# LaserDiode_Analog.net
KiCad netlist of a schematic drawn in Altium Designer
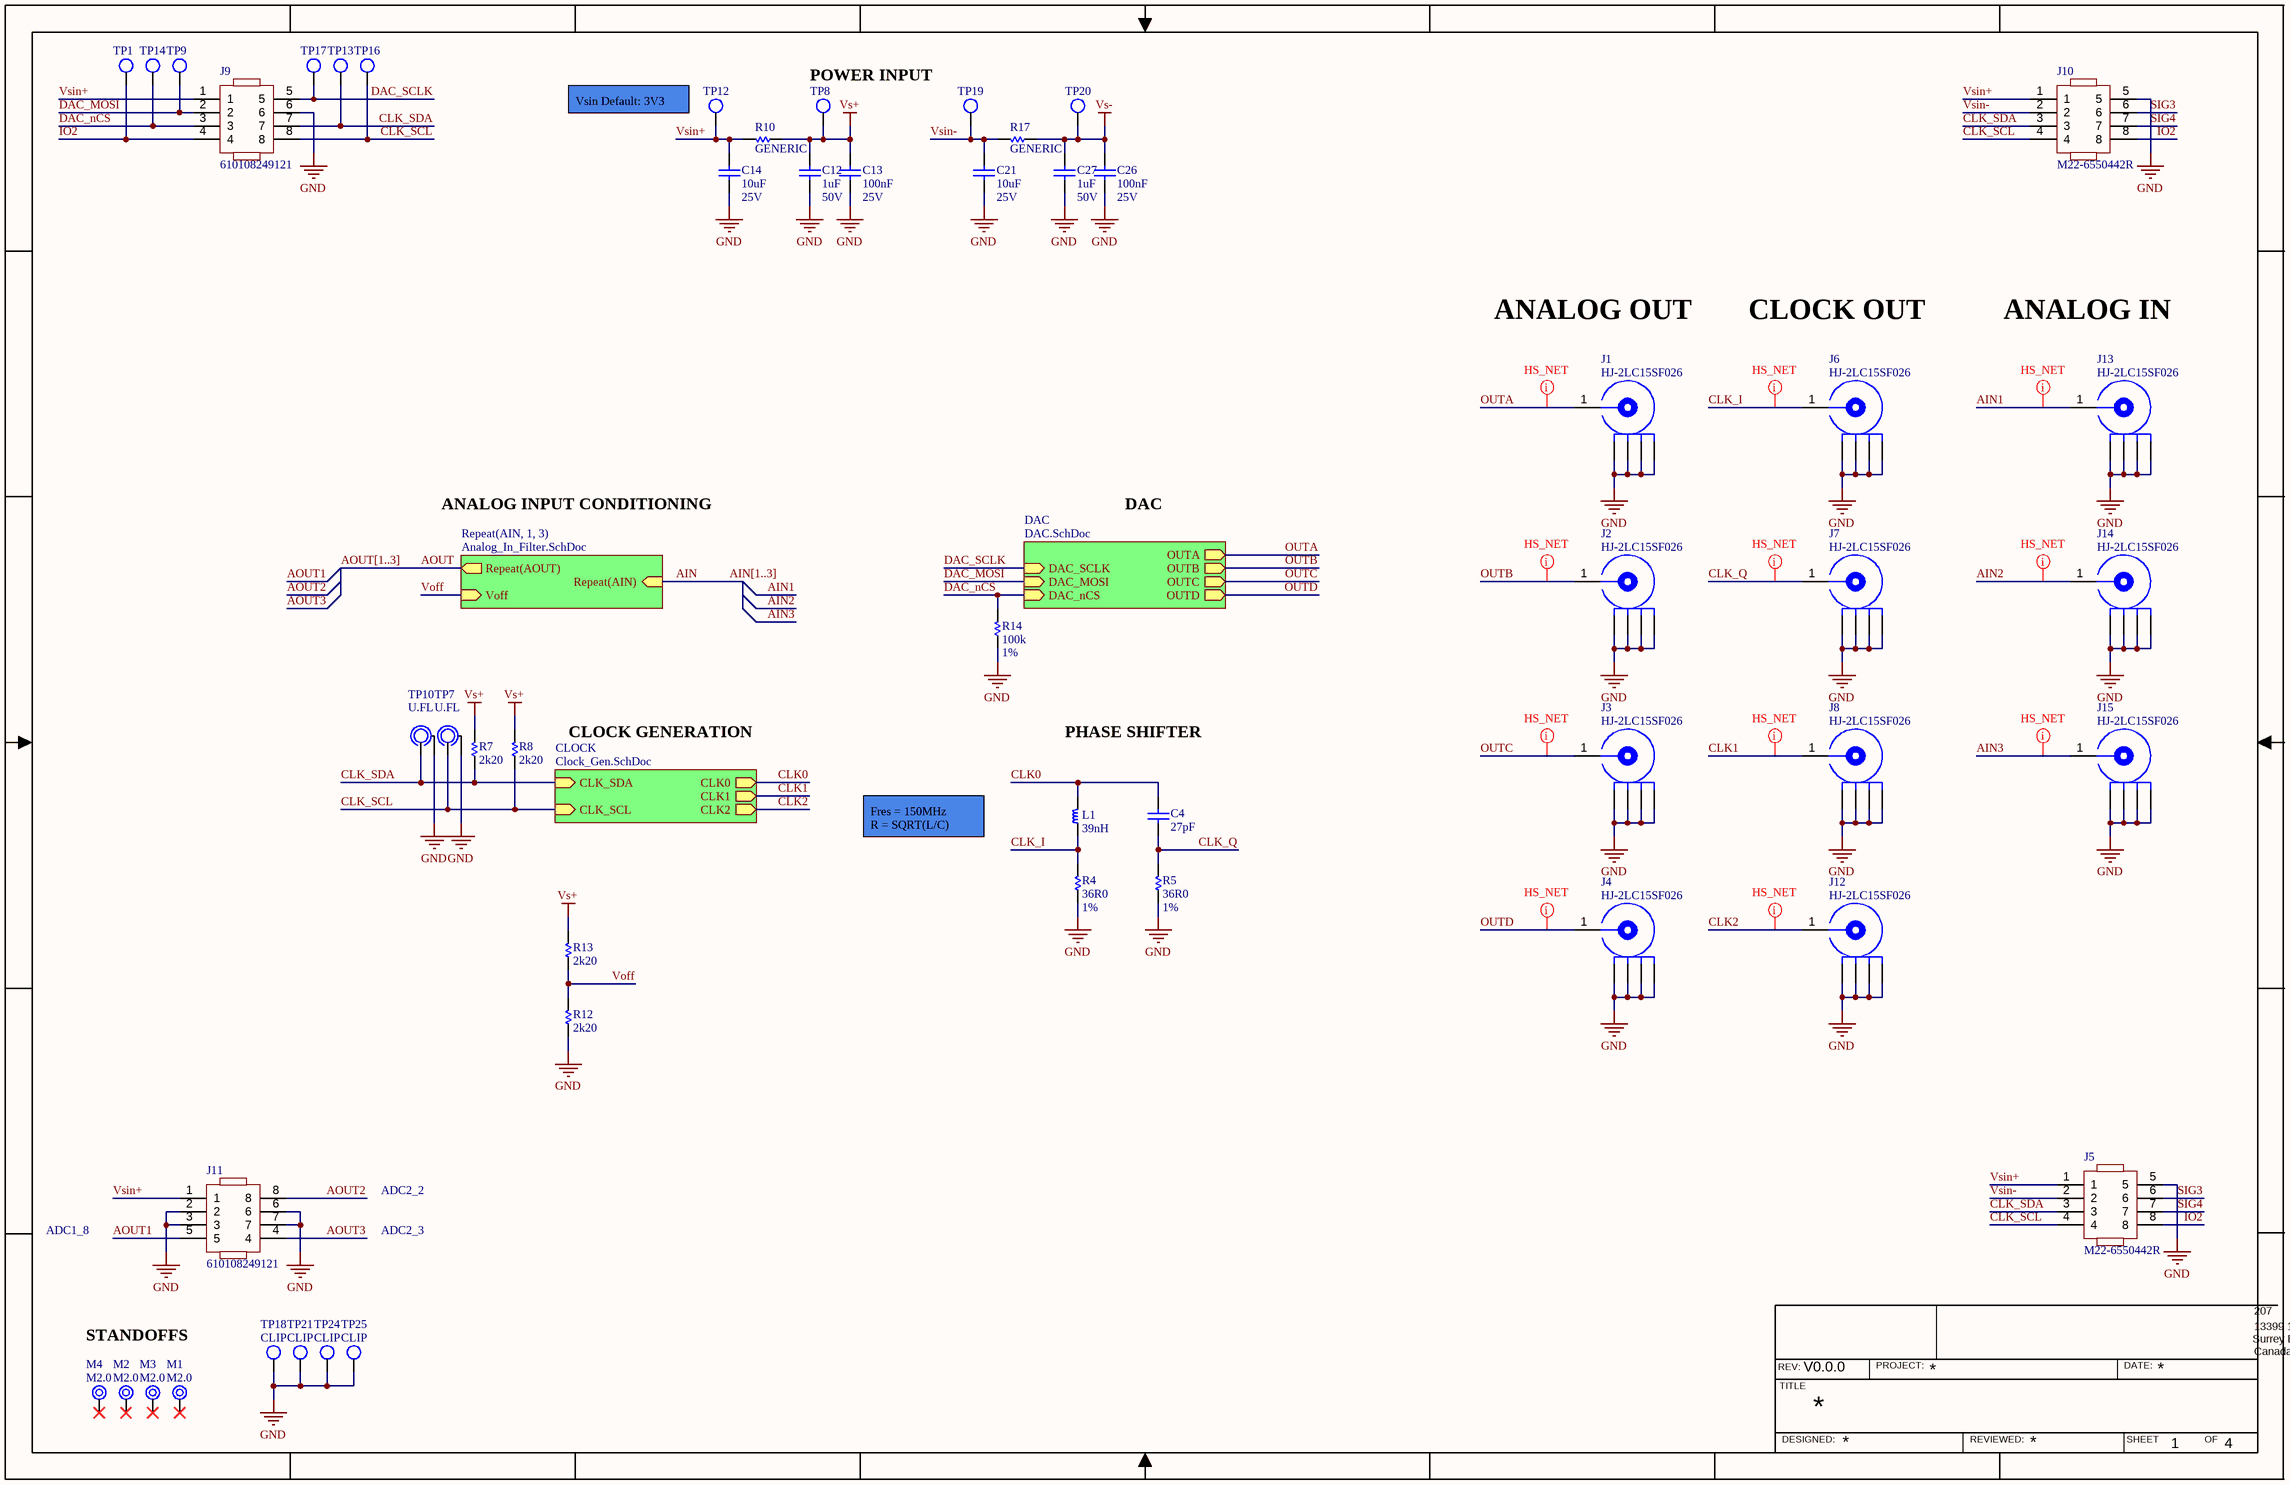
[diagram p0: LaserDiode_Analog.SchDoc]

(export (version "E")
  (design (tool "Eeschema 10.0.6"))
  (components
    (comp (ref "C4")
      (value "27pF")
      (footprint "C0402")
      (description "贴片陶瓷电容  27pF ±5% 50V C0G(NP0) 0402")
      (fields
        (field (name "MANUFACTURER") "Samsung")
        (field (name "MANUFACTURER PART NUMBER") "CL05C270JB5NNNC")
      )
      (libsource (lib "LaserDiode_Analog") (part "CAP CER 27pF 50V C0G 0402"))
    )
    (comp (ref "C12")
      (value "1uF")
      (footprint "c0603")
      (description "Multilayer Ceramic Capacitors (High dielectric type), 50V, 1 uF, ± 10 %, 0603, X5R, RoHS")
      (fields
        (field (name "MANUFACTURER") "Taiyo Yuden")
        (field (name "MANUFACTURER PART NUMBER") "UMK107BJ105KA-T")
        (field (name "VOLTAGE RATING") "50V")
      )
      (libsource (lib "OPAMP_DEV_SOT5_6-23") (part "CAP CER 1uF 50V X5R 0603"))
    )
    (comp (ref "C13")
      (value "100nF")
      (footprint "C0402")
      (description "Cap Ceramic 0.1uF 25V X5R 10% Pad SMD 0402 85°C T/R / Multi Layer Ceramic Capacitor (MLCC)")
      (fields
        (field (name "MANUFACTURER") "Samsung")
        (field (name "MANUFACTURER PART NUMBER") "CL05A104KA5NNNC")
        (field (name "VOLTAGE RATING") "25V")
      )
      (libsource (lib "OPAMP_DEV_SOT5_6-23") (part "CAP CER 100nF 25V X5R 0402"))
    )
    (comp (ref "C14")
      (value "10uF")
      (footprint "c0805")
      (description "Cap Ceramic 10uF 25V X5R 10% SMD 0805 85°C Embossed T/R")
      (fields
        (field (name "MANUFACTURER") "Samsung")
        (field (name "MANUFACTURER PART NUMBER") "CL21A106KAYNNNE")
        (field (name "VOLTAGE RATING") "25V")
      )
      (libsource (lib "OPAMP_DEV_SOT5_6-23") (part "CAP CER 10uF 25V X5R 0805"))
    )
    (comp (ref "C21")
      (value "10uF")
      (footprint "c0805")
      (description "Cap Ceramic 10uF 25V X5R 10% SMD 0805 85°C Embossed T/R")
      (fields
        (field (name "MANUFACTURER") "Samsung")
        (field (name "MANUFACTURER PART NUMBER") "CL21A106KAYNNNE")
        (field (name "VOLTAGE RATING") "25V")
      )
      (libsource (lib "OPAMP_DEV_SOT5_6-23") (part "CAP CER 10uF 25V X5R 0805"))
    )
    (comp (ref "C26")
      (value "100nF")
      (footprint "C0402")
      (description "Cap Ceramic 0.1uF 25V X5R 10% Pad SMD 0402 85°C T/R / Multi Layer Ceramic Capacitor (MLCC)")
      (fields
        (field (name "MANUFACTURER") "Samsung")
        (field (name "MANUFACTURER PART NUMBER") "CL05A104KA5NNNC")
        (field (name "VOLTAGE RATING") "25V")
      )
      (libsource (lib "OPAMP_DEV_SOT5_6-23") (part "CAP CER 100nF 25V X5R 0402"))
    )
    (comp (ref "C27")
      (value "1uF")
      (footprint "c0603")
      (description "Multilayer Ceramic Capacitors (High dielectric type), 50V, 1 uF, ± 10 %, 0603, X5R, RoHS")
      (fields
        (field (name "MANUFACTURER") "Taiyo Yuden")
        (field (name "MANUFACTURER PART NUMBER") "UMK107BJ105KA-T")
        (field (name "VOLTAGE RATING") "50V")
      )
      (libsource (lib "OPAMP_DEV_SOT5_6-23") (part "CAP CER 1uF 50V X5R 0603"))
    )
    (comp (ref "J1")
      (value "HJ-2LC15SF026")
      (footprint "SMA TH RA BORE")
      (libsource (lib "LaserDiode_Analog") (part "CON SMA BORE SMD RA HJ-2LC15SF026"))
    )
    (comp (ref "J2")
      (value "HJ-2LC15SF026")
      (footprint "SMA TH RA BORE")
      (libsource (lib "LaserDiode_Analog") (part "CON SMA BORE SMD RA HJ-2LC15SF026"))
    )
    (comp (ref "J3")
      (value "HJ-2LC15SF026")
      (footprint "SMA TH RA BORE")
      (libsource (lib "LaserDiode_Analog") (part "CON SMA BORE SMD RA HJ-2LC15SF026"))
    )
    (comp (ref "J4")
      (value "HJ-2LC15SF026")
      (footprint "SMA TH RA BORE")
      (libsource (lib "LaserDiode_Analog") (part "CON SMA BORE SMD RA HJ-2LC15SF026"))
    )
    (comp (ref "J5")
      (value "M22-6550442R")
      (footprint "CONN HDR 08 FEMALE RA 2ROW")
      (description "Conn Socket Strip RCP 8 POS 2mm Solder RA SMD T/R")
      (fields (field (name "MANUFACTURER") "Harwin"))
      (libsource (lib "OPAMP_DEV_SOT5_6-23") (part "CONN HDR 08 FEMALE RA 2 ROW"))
    )
    (comp (ref "J6")
      (value "HJ-2LC15SF026")
      (footprint "SMA TH RA BORE")
      (libsource (lib "LaserDiode_Analog") (part "CON SMA BORE SMD RA HJ-2LC15SF026"))
    )
    (comp (ref "J7")
      (value "HJ-2LC15SF026")
      (footprint "SMA TH RA BORE")
      (libsource (lib "LaserDiode_Analog") (part "CON SMA BORE SMD RA HJ-2LC15SF026"))
    )
    (comp (ref "J8")
      (value "HJ-2LC15SF026")
      (footprint "SMA TH RA BORE")
      (libsource (lib "LaserDiode_Analog") (part "CON SMA BORE SMD RA HJ-2LC15SF026"))
    )
    (comp (ref "J9")
      (value "610108249121")
      (footprint "CONN HDR 08 MALE RA 2ROW - duplicate")
      (description "SMT Angled Pin Header WR-PHD, Pitch 2.54 mm, Dual Row, 8 pins")
      (fields (field (name "MANUFACTURER") "Wurth Electronics"))
      (libsource (lib "") (part "CONN HDR 08 MALE RA 2 ROW_1"))
    )
    (comp (ref "J10")
      (value "M22-6550442R")
      (footprint "CONN HDR 08 FEMALE RA 2ROW")
      (description "Conn Socket Strip RCP 8 POS 2mm Solder RA SMD T/R")
      (fields (field (name "MANUFACTURER") "Harwin"))
      (libsource (lib "OPAMP_DEV_SOT5_6-23") (part "CONN HDR 08 FEMALE RA 2 ROW"))
    )
    (comp (ref "J11")
      (value "610108249121")
      (footprint "CONN HDR 08 MALE RA 2ROW - duplicate")
      (description "SMT Angled Pin Header WR-PHD, Pitch 2.54 mm, Dual Row, 8 pins")
      (fields (field (name "MANUFACTURER") "Wurth Electronics"))
      (libsource (lib "OPAMP_DEV_SOT5_6-23") (part "CONN HDR 08 MALE RA 2 ROW"))
    )
    (comp (ref "J12")
      (value "HJ-2LC15SF026")
      (footprint "SMA TH RA BORE")
      (libsource (lib "LaserDiode_Analog") (part "CON SMA BORE SMD RA HJ-2LC15SF026"))
    )
    (comp (ref "J13")
      (value "HJ-2LC15SF026")
      (footprint "SMA TH RA BORE")
      (libsource (lib "LaserDiode_Analog") (part "CON SMA BORE SMD RA HJ-2LC15SF026"))
    )
    (comp (ref "J14")
      (value "HJ-2LC15SF026")
      (footprint "SMA TH RA BORE")
      (libsource (lib "LaserDiode_Analog") (part "CON SMA BORE SMD RA HJ-2LC15SF026"))
    )
    (comp (ref "J15")
      (value "HJ-2LC15SF026")
      (footprint "SMA TH RA BORE")
      (libsource (lib "LaserDiode_Analog") (part "CON SMA BORE SMD RA HJ-2LC15SF026"))
    )
    (comp (ref "L1")
      (value "39nH")
      (footprint "L0402")
      (description "Inductor RF Chip Multi-Layer 0.039uH 5% 100MHz 8Q-Factor Ceramic 0.15A 1.2Ohm DCR 0402 T/R")
      (fields (field (name "TOLERANCE") "5%"))
      (libsource (lib "LaserDiode_Analog") (part "IND HF 39nH 5% 150mA 1R2 0402"))
    )
    (comp (ref "M1")
      (value "M2.0")
      (footprint "MECH M2.0 UNPLATED")
      (libsource (lib "OPAMP_DEV_SOT5_6-23") (part "MECH M2.0 UNPLATED"))
    )
    (comp (ref "M2")
      (value "M2.0")
      (footprint "MECH M2.0 UNPLATED")
      (libsource (lib "OPAMP_DEV_SOT5_6-23") (part "MECH M2.0 UNPLATED"))
    )
    (comp (ref "M3")
      (value "M2.0")
      (footprint "MECH M2.0 UNPLATED")
      (libsource (lib "OPAMP_DEV_SOT5_6-23") (part "MECH M2.0 UNPLATED"))
    )
    (comp (ref "M4")
      (value "M2.0")
      (footprint "MECH M2.0 UNPLATED")
      (libsource (lib "OPAMP_DEV_SOT5_6-23") (part "MECH M2.0 UNPLATED"))
    )
    (comp (ref "R4")
      (value "36R0")
      (footprint "R0402")
      (description "Res Thick Film 0402 36 Ohm 1% 0.063W(1/16W) ±100ppm/°C Pad SMD T/R")
      (fields (field (name "TOLERANCE") "1%"))
      (libsource (lib "LaserDiode_Analog") (part "RES 36R0 1% 63mW 0402"))
    )
    (comp (ref "R5")
      (value "36R0")
      (footprint "R0402")
      (description "Res Thick Film 0402 36 Ohm 1% 0.063W(1/16W) ±100ppm/°C Pad SMD T/R")
      (fields (field (name "TOLERANCE") "1%"))
      (libsource (lib "LaserDiode_Analog") (part "RES 36R0 1% 63mW 0402"))
    )
    (comp (ref "R7")
      (value "2k20")
      (footprint "R0402")
      (description "贴片电阻 2200Ω ± 1.00% 0.0625W ± 100ppm/℃ 0402")
      (fields
        (field (name "MANUFACTURER") "Yageo")
        (field (name "MANUFACTURER PART NUMBER") "RC0402FR-072K2L")
      )
      (libsource (lib "LaserDiode_Analog") (part "RES 2k20 1% 63mW 0402"))
    )
    (comp (ref "R8")
      (value "2k20")
      (footprint "R0402")
      (description "贴片电阻 2200Ω ± 1.00% 0.0625W ± 100ppm/℃ 0402")
      (fields
        (field (name "MANUFACTURER") "Yageo")
        (field (name "MANUFACTURER PART NUMBER") "RC0402FR-072K2L")
      )
      (libsource (lib "LaserDiode_Analog") (part "RES 2k20 1% 63mW 0402"))
    )
    (comp (ref "R10")
      (value "GENERIC")
      (footprint "R0603")
      (libsource (lib "OPAMP_DEV_SOT5_6-23") (part "RES GENERIC 0603"))
    )
    (comp (ref "R12")
      (value "2k20")
      (footprint "R0402")
      (description "贴片电阻 2200Ω ± 1.00% 0.0625W ± 100ppm/℃ 0402")
      (fields
        (field (name "MANUFACTURER") "Yageo")
        (field (name "MANUFACTURER PART NUMBER") "RC0402FR-072K2L")
      )
      (libsource (lib "LaserDiode_Analog") (part "RES 2k20 1% 63mW 0402"))
    )
    (comp (ref "R13")
      (value "2k20")
      (footprint "R0402")
      (description "贴片电阻 2200Ω ± 1.00% 0.0625W ± 100ppm/℃ 0402")
      (fields
        (field (name "MANUFACTURER") "Yageo")
        (field (name "MANUFACTURER PART NUMBER") "RC0402FR-072K2L")
      )
      (libsource (lib "LaserDiode_Analog") (part "RES 2k20 1% 63mW 0402"))
    )
    (comp (ref "R14")
      (value "100k")
      (footprint "r0402")
      (description "Res Thick Film 0402 100K Ohm 1% 0.063W ±100ppm/°C Molded SMD Paper T/R")
      (fields
        (field (name "MANUFACTURER") "Stackpole Electronics")
        (field (name "MANUFACTURER PART NUMBER") "RMCF0402FT100K")
        (field (name "TOLERANCE") "1%")
      )
      (libsource (lib "LaserDiode_Analog") (part "RES 100k 1% 63mW 0402"))
    )
    (comp (ref "R17")
      (value "GENERIC")
      (footprint "R0603")
      (libsource (lib "OPAMP_DEV_SOT5_6-23") (part "RES GENERIC 0603"))
    )
    (comp (ref "TP1")
      (value "1mm")
      (footprint "TESTPOINT_SMT")
      (description "SMT testpoint")
      (libsource (lib "OPAMP_DEV_SOT5_6-23") (part "TP 1mm"))
    )
    (comp (ref "TP7")
      (value "U.FL")
      (footprint "U.FL")
      (description "CONN U.FL RCPT STR 50 OHM SMD")
      (fields
        (field (name "MANUFACTURER") "Hirose")
        (field (name "MANUFACTURER PART NUMBER") "U.FL-R-SMT-1(80)")
      )
      (libsource (lib "OPAMP_DEV_SOT5_6-23") (part "TP U.FL"))
    )
    (comp (ref "TP8")
      (value "1mm")
      (footprint "TESTPOINT_SMT")
      (description "SMT testpoint")
      (libsource (lib "OPAMP_DEV_SOT5_6-23") (part "TP 1mm"))
    )
    (comp (ref "TP9")
      (value "1mm")
      (footprint "TESTPOINT_SMT")
      (description "SMT testpoint")
      (libsource (lib "OPAMP_DEV_SOT5_6-23") (part "TP 1mm"))
    )
    (comp (ref "TP10")
      (value "U.FL")
      (footprint "U.FL")
      (description "CONN U.FL RCPT STR 50 OHM SMD")
      (fields
        (field (name "MANUFACTURER") "Hirose")
        (field (name "MANUFACTURER PART NUMBER") "U.FL-R-SMT-1(80)")
      )
      (libsource (lib "OPAMP_DEV_SOT5_6-23") (part "TP U.FL"))
    )
    (comp (ref "TP12")
      (value "1mm")
      (footprint "TESTPOINT_SMT")
      (description "SMT testpoint")
      (libsource (lib "OPAMP_DEV_SOT5_6-23") (part "TP 1mm"))
    )
    (comp (ref "TP13")
      (value "1mm")
      (footprint "TESTPOINT_SMT")
      (description "SMT testpoint")
      (libsource (lib "OPAMP_DEV_SOT5_6-23") (part "TP 1mm"))
    )
    (comp (ref "TP14")
      (value "1mm")
      (footprint "TESTPOINT_SMT")
      (description "SMT testpoint")
      (libsource (lib "OPAMP_DEV_SOT5_6-23") (part "TP 1mm"))
    )
    (comp (ref "TP16")
      (value "1mm")
      (footprint "TESTPOINT_SMT")
      (description "SMT testpoint")
      (libsource (lib "OPAMP_DEV_SOT5_6-23") (part "TP 1mm"))
    )
    (comp (ref "TP17")
      (value "1mm")
      (footprint "TESTPOINT_SMT")
      (description "SMT testpoint")
      (libsource (lib "OPAMP_DEV_SOT5_6-23") (part "TP 1mm"))
    )
    (comp (ref "TP18")
      (value "CLIP")
      (footprint "TESTPOINT_CLIP_1206")
      (description "Current Sense Resistors - SMD CHIP CHECKER HT=2.0 1206")
      (fields (field (name "MANUFACTURER") "KOA Speer") (field (name "MANUFACTURER PART NUMBER") "RCWCTE"))
      (libsource (lib "LaserDiode_Analog") (part "TP CLIP 1206 RCWCTE"))
    )
    (comp (ref "TP19")
      (value "1mm")
      (footprint "TESTPOINT_SMT")
      (description "SMT testpoint")
      (libsource (lib "OPAMP_DEV_SOT5_6-23") (part "TP 1mm"))
    )
    (comp (ref "TP20")
      (value "1mm")
      (footprint "TESTPOINT_SMT")
      (description "SMT testpoint")
      (libsource (lib "OPAMP_DEV_SOT5_6-23") (part "TP 1mm"))
    )
    (comp (ref "TP21")
      (value "CLIP")
      (footprint "TESTPOINT_CLIP_1206")
      (description "Current Sense Resistors - SMD CHIP CHECKER HT=2.0 1206")
      (fields (field (name "MANUFACTURER") "KOA Speer") (field (name "MANUFACTURER PART NUMBER") "RCWCTE"))
      (libsource (lib "LaserDiode_Analog") (part "TP CLIP 1206 RCWCTE"))
    )
    (comp (ref "TP24")
      (value "CLIP")
      (footprint "TESTPOINT_CLIP_1206")
      (description "Current Sense Resistors - SMD CHIP CHECKER HT=2.0 1206")
      (fields (field (name "MANUFACTURER") "KOA Speer") (field (name "MANUFACTURER PART NUMBER") "RCWCTE"))
      (libsource (lib "LaserDiode_Analog") (part "TP CLIP 1206 RCWCTE"))
    )
    (comp (ref "TP25")
      (value "CLIP")
      (footprint "TESTPOINT_CLIP_1206")
      (description "Current Sense Resistors - SMD CHIP CHECKER HT=2.0 1206")
      (fields (field (name "MANUFACTURER") "KOA Speer") (field (name "MANUFACTURER PART NUMBER") "RCWCTE"))
      (libsource (lib "LaserDiode_Analog") (part "TP CLIP 1206 RCWCTE"))
    )
  )
  (nets
    (net (code "2") (name "/AIN1") (class "Default")
      (node (ref "J13") (pin "1") (pinfunction "1_1") (pintype "passive"))
    )
    (net (code "3") (name "/AIN2") (class "Default")
      (node (ref "J14") (pin "1") (pinfunction "1_1") (pintype "passive"))
    )
    (net (code "4") (name "/AIN3") (class "Default")
      (node (ref "J15") (pin "1") (pinfunction "1_1") (pintype "passive"))
    )
    (net (code "7") (name "/AOUT1") (class "Default")
      (node (ref "J11") (pin "5") (pinfunction "5_5") (pintype "passive"))
    )
    (net (code "8") (name "/AOUT2") (class "Default")
      (node (ref "J11") (pin "8") (pinfunction "8_8") (pintype "passive"))
    )
    (net (code "9") (name "/AOUT3") (class "Default")
      (node (ref "J11") (pin "4") (pinfunction "4_4") (pintype "passive"))
    )
    (net (code "11") (name "/CLK0") (class "Default")
      (node (ref "C4") (pin "2") (pinfunction "2_2") (pintype "passive"))
      (node (ref "L1") (pin "1") (pinfunction "1_1") (pintype "passive"))
    )
    (net (code "12") (name "/CLK1") (class "Default")
      (node (ref "J8") (pin "1") (pinfunction "1_1") (pintype "passive"))
    )
    (net (code "13") (name "/CLK2") (class "Default")
      (node (ref "J12") (pin "1") (pinfunction "1_1") (pintype "passive"))
    )
    (net (code "14") (name "/CLK_I") (class "Default")
      (node (ref "J6") (pin "1") (pinfunction "1_1") (pintype "passive"))
      (node (ref "L1") (pin "2") (pinfunction "2_2") (pintype "passive"))
      (node (ref "R4") (pin "2") (pinfunction "2_2") (pintype "passive"))
    )
    (net (code "15") (name "/CLK_Q") (class "Default")
      (node (ref "C4") (pin "1") (pinfunction "1_1") (pintype "passive"))
      (node (ref "J7") (pin "1") (pinfunction "1_1") (pintype "passive"))
      (node (ref "R5") (pin "2") (pinfunction "2_2") (pintype "passive"))
    )
    (net (code "16") (name "/CLK_SCL") (class "Default")
      (node (ref "J10") (pin "4") (pinfunction "4_4") (pintype "passive"))
      (node (ref "J5") (pin "4") (pinfunction "4_4") (pintype "passive"))
      (node (ref "J9") (pin "8") (pinfunction "8_8") (pintype "passive"))
      (node (ref "R8") (pin "1") (pinfunction "1_1") (pintype "passive"))
      (node (ref "TP16") (pin "1") (pinfunction "1_1") (pintype "passive"))
      (node (ref "TP7") (pin "1") (pinfunction "1_1") (pintype "passive"))
    )
    (net (code "17") (name "/CLK_SDA") (class "Default")
      (node (ref "J10") (pin "3") (pinfunction "3_3") (pintype "passive"))
      (node (ref "J5") (pin "3") (pinfunction "3_3") (pintype "passive"))
      (node (ref "J9") (pin "7") (pinfunction "7_7") (pintype "passive"))
      (node (ref "R7") (pin "1") (pinfunction "1_1") (pintype "passive"))
      (node (ref "TP10") (pin "1") (pinfunction "1_1") (pintype "passive"))
      (node (ref "TP13") (pin "1") (pinfunction "1_1") (pintype "passive"))
    )
    (net (code "18") (name "/DAC_MOSI") (class "Default")
      (node (ref "J9") (pin "2") (pinfunction "2_2") (pintype "passive"))
      (node (ref "TP9") (pin "1") (pinfunction "1_1") (pintype "passive"))
    )
    (net (code "19") (name "/DAC_SCLK") (class "Default")
      (node (ref "J9") (pin "5") (pinfunction "5_5") (pintype "passive"))
      (node (ref "TP17") (pin "1") (pinfunction "1_1") (pintype "passive"))
    )
    (net (code "20") (name "/DAC_nCS") (class "Default")
      (node (ref "J9") (pin "3") (pinfunction "3_3") (pintype "passive"))
      (node (ref "R14") (pin "2") (pinfunction "2_2") (pintype "passive"))
      (node (ref "TP14") (pin "1") (pinfunction "1_1") (pintype "passive"))
    )
    (net (code "21") (name "/IO2") (class "Default")
      (node (ref "J10") (pin "8") (pinfunction "8_8") (pintype "passive"))
      (node (ref "J5") (pin "8") (pinfunction "8_8") (pintype "passive"))
      (node (ref "J9") (pin "4") (pinfunction "4_4") (pintype "passive"))
      (node (ref "TP1") (pin "1") (pinfunction "1_1") (pintype "passive"))
    )
    (net (code "22") (name "/OUTA") (class "Default")
      (node (ref "J1") (pin "1") (pinfunction "1_1") (pintype "passive"))
    )
    (net (code "23") (name "/OUTB") (class "Default")
      (node (ref "J2") (pin "1") (pinfunction "1_1") (pintype "passive"))
    )
    (net (code "24") (name "/OUTC") (class "Default")
      (node (ref "J3") (pin "1") (pinfunction "1_1") (pintype "passive"))
    )
    (net (code "25") (name "/OUTD") (class "Default")
      (node (ref "J4") (pin "1") (pinfunction "1_1") (pintype "passive"))
    )
    (net (code "26") (name "/SIG3") (class "Default")
      (node (ref "J10") (pin "6") (pinfunction "6_6") (pintype "passive"))
      (node (ref "J5") (pin "6") (pinfunction "6_6") (pintype "passive"))
    )
    (net (code "27") (name "/SIG4") (class "Default")
      (node (ref "J10") (pin "7") (pinfunction "7_7") (pintype "passive"))
      (node (ref "J5") (pin "7") (pinfunction "7_7") (pintype "passive"))
    )
    (net (code "28") (name "/Voff") (class "Default")
      (node (ref "R12") (pin "2") (pinfunction "2_2") (pintype "passive"))
      (node (ref "R13") (pin "1") (pinfunction "1_1") (pintype "passive"))
    )
    (net (code "29") (name "/Vsin+") (class "Default")
      (node (ref "C14") (pin "2") (pinfunction "2_2") (pintype "passive"))
      (node (ref "J10") (pin "1") (pinfunction "1_1") (pintype "passive"))
      (node (ref "J11") (pin "1") (pinfunction "1_1") (pintype "passive"))
      (node (ref "J5") (pin "1") (pinfunction "1_1") (pintype "passive"))
      (node (ref "J9") (pin "1") (pinfunction "1_1") (pintype "passive"))
      (node (ref "R10") (pin "2") (pinfunction "2_2") (pintype "passive"))
      (node (ref "TP12") (pin "1") (pinfunction "1_1") (pintype "passive"))
    )
    (net (code "30") (name "/Vsin-") (class "Default")
      (node (ref "C21") (pin "2") (pinfunction "2_2") (pintype "passive"))
      (node (ref "J10") (pin "2") (pinfunction "2_2") (pintype "passive"))
      (node (ref "J5") (pin "2") (pinfunction "2_2") (pintype "passive"))
      (node (ref "R17") (pin "2") (pinfunction "2_2") (pintype "passive"))
      (node (ref "TP19") (pin "1") (pinfunction "1_1") (pintype "passive"))
    )
    (net (code "31") (name "GND") (class "Default")
      (node (ref "C12") (pin "1") (pinfunction "1_1") (pintype "passive"))
      (node (ref "C13") (pin "1") (pinfunction "1_1") (pintype "passive"))
      (node (ref "C14") (pin "1") (pinfunction "1_1") (pintype "passive"))
      (node (ref "C21") (pin "1") (pinfunction "1_1") (pintype "passive"))
      (node (ref "C26") (pin "1") (pinfunction "1_1") (pintype "passive"))
      (node (ref "C27") (pin "1") (pinfunction "1_1") (pintype "passive"))
      (node (ref "J1") (pin "0") (pinfunction "5_0") (pintype "passive"))
      (node (ref "J10") (pin "5") (pinfunction "5_5") (pintype "passive"))
      (node (ref "J11") (pin "2") (pinfunction "2_2") (pintype "passive"))
      (node (ref "J11") (pin "3") (pinfunction "3_3") (pintype "passive"))
      (node (ref "J11") (pin "6") (pinfunction "6_6") (pintype "passive"))
      (node (ref "J11") (pin "7") (pinfunction "7_7") (pintype "passive"))
      (node (ref "J12") (pin "0") (pinfunction "3_0") (pintype "passive"))
      (node (ref "J13") (pin "0") (pinfunction "5_0") (pintype "passive"))
      (node (ref "J14") (pin "0") (pinfunction "3_0") (pintype "passive"))
      (node (ref "J15") (pin "0") (pinfunction "2_0") (pintype "passive"))
      (node (ref "J2") (pin "0") (pinfunction "5_0") (pintype "passive"))
      (node (ref "J3") (pin "0") (pinfunction "5_0") (pintype "passive"))
      (node (ref "J4") (pin "0") (pinfunction "2_0") (pintype "passive"))
      (node (ref "J5") (pin "5") (pinfunction "5_5") (pintype "passive"))
      (node (ref "J6") (pin "0") (pinfunction "4_0") (pintype "passive"))
      (node (ref "J7") (pin "0") (pinfunction "5_0") (pintype "passive"))
      (node (ref "J8") (pin "0") (pinfunction "5_0") (pintype "passive"))
      (node (ref "J9") (pin "6") (pinfunction "6_6") (pintype "passive"))
      (node (ref "R12") (pin "1") (pinfunction "1_1") (pintype "passive"))
      (node (ref "R14") (pin "1") (pinfunction "1_1") (pintype "passive"))
      (node (ref "R4") (pin "1") (pinfunction "1_1") (pintype "passive"))
      (node (ref "R5") (pin "1") (pinfunction "1_1") (pintype "passive"))
      (node (ref "TP10") (pin "0") (pinfunction "0_0") (pintype "passive"))
      (node (ref "TP18") (pin "1") (pinfunction "1_1") (pintype "passive"))
      (node (ref "TP21") (pin "1") (pinfunction "1_1") (pintype "passive"))
      (node (ref "TP24") (pin "1") (pinfunction "1_1") (pintype "passive"))
      (node (ref "TP25") (pin "1") (pinfunction "1_1") (pintype "passive"))
      (node (ref "TP7") (pin "0") (pinfunction "0_0") (pintype "passive"))
    )
    (net (code "32") (name "Vs+") (class "Default")
      (node (ref "C12") (pin "2") (pinfunction "2_2") (pintype "passive"))
      (node (ref "C13") (pin "2") (pinfunction "2_2") (pintype "passive"))
      (node (ref "R10") (pin "1") (pinfunction "1_1") (pintype "passive"))
      (node (ref "R13") (pin "2") (pinfunction "2_2") (pintype "passive"))
      (node (ref "R7") (pin "2") (pinfunction "2_2") (pintype "passive"))
      (node (ref "R8") (pin "2") (pinfunction "2_2") (pintype "passive"))
      (node (ref "TP8") (pin "1") (pinfunction "1_1") (pintype "passive"))
    )
    (net (code "33") (name "Vs-") (class "Default")
      (node (ref "C26") (pin "2") (pinfunction "2_2") (pintype "passive"))
      (node (ref "C27") (pin "2") (pinfunction "2_2") (pintype "passive"))
      (node (ref "R17") (pin "1") (pinfunction "1_1") (pintype "passive"))
      (node (ref "TP20") (pin "1") (pinfunction "1_1") (pintype "passive"))
    )
    (net (code "34") (name "unconnected-(M1-Pad1)") (class "Default")
      (node (ref "M1") (pin "1") (pinfunction "1_1") (pintype "passive+no_connect"))
    )
    (net (code "35") (name "unconnected-(M2-Pad1)") (class "Default")
      (node (ref "M2") (pin "1") (pinfunction "1_1") (pintype "passive+no_connect"))
    )
    (net (code "36") (name "unconnected-(M3-Pad1)") (class "Default")
      (node (ref "M3") (pin "1") (pinfunction "1_1") (pintype "passive+no_connect"))
    )
    (net (code "37") (name "unconnected-(M4-Pad1)") (class "Default")
      (node (ref "M4") (pin "1") (pinfunction "1_1") (pintype "passive+no_connect"))
    )
  )
)
